# Airbeam_v2_4_12-21-2017.net
KiCad netlist of a schematic drawn in EAGLE
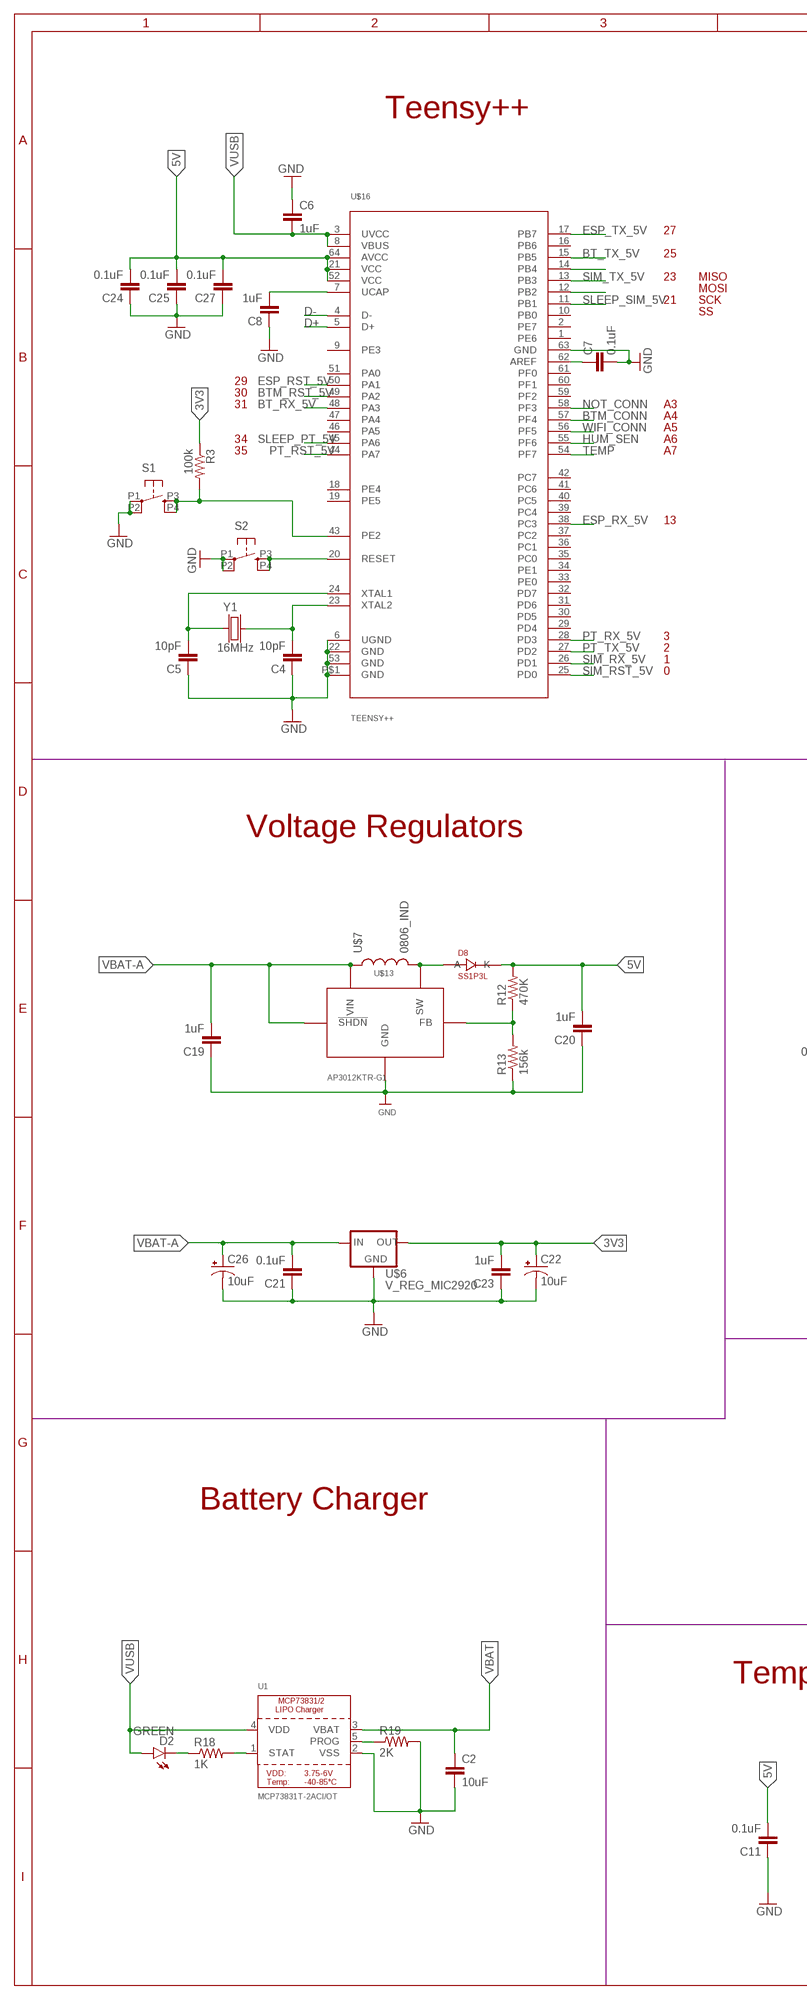
[diagram p0: schematic, sheet 1, part 1 of 2]
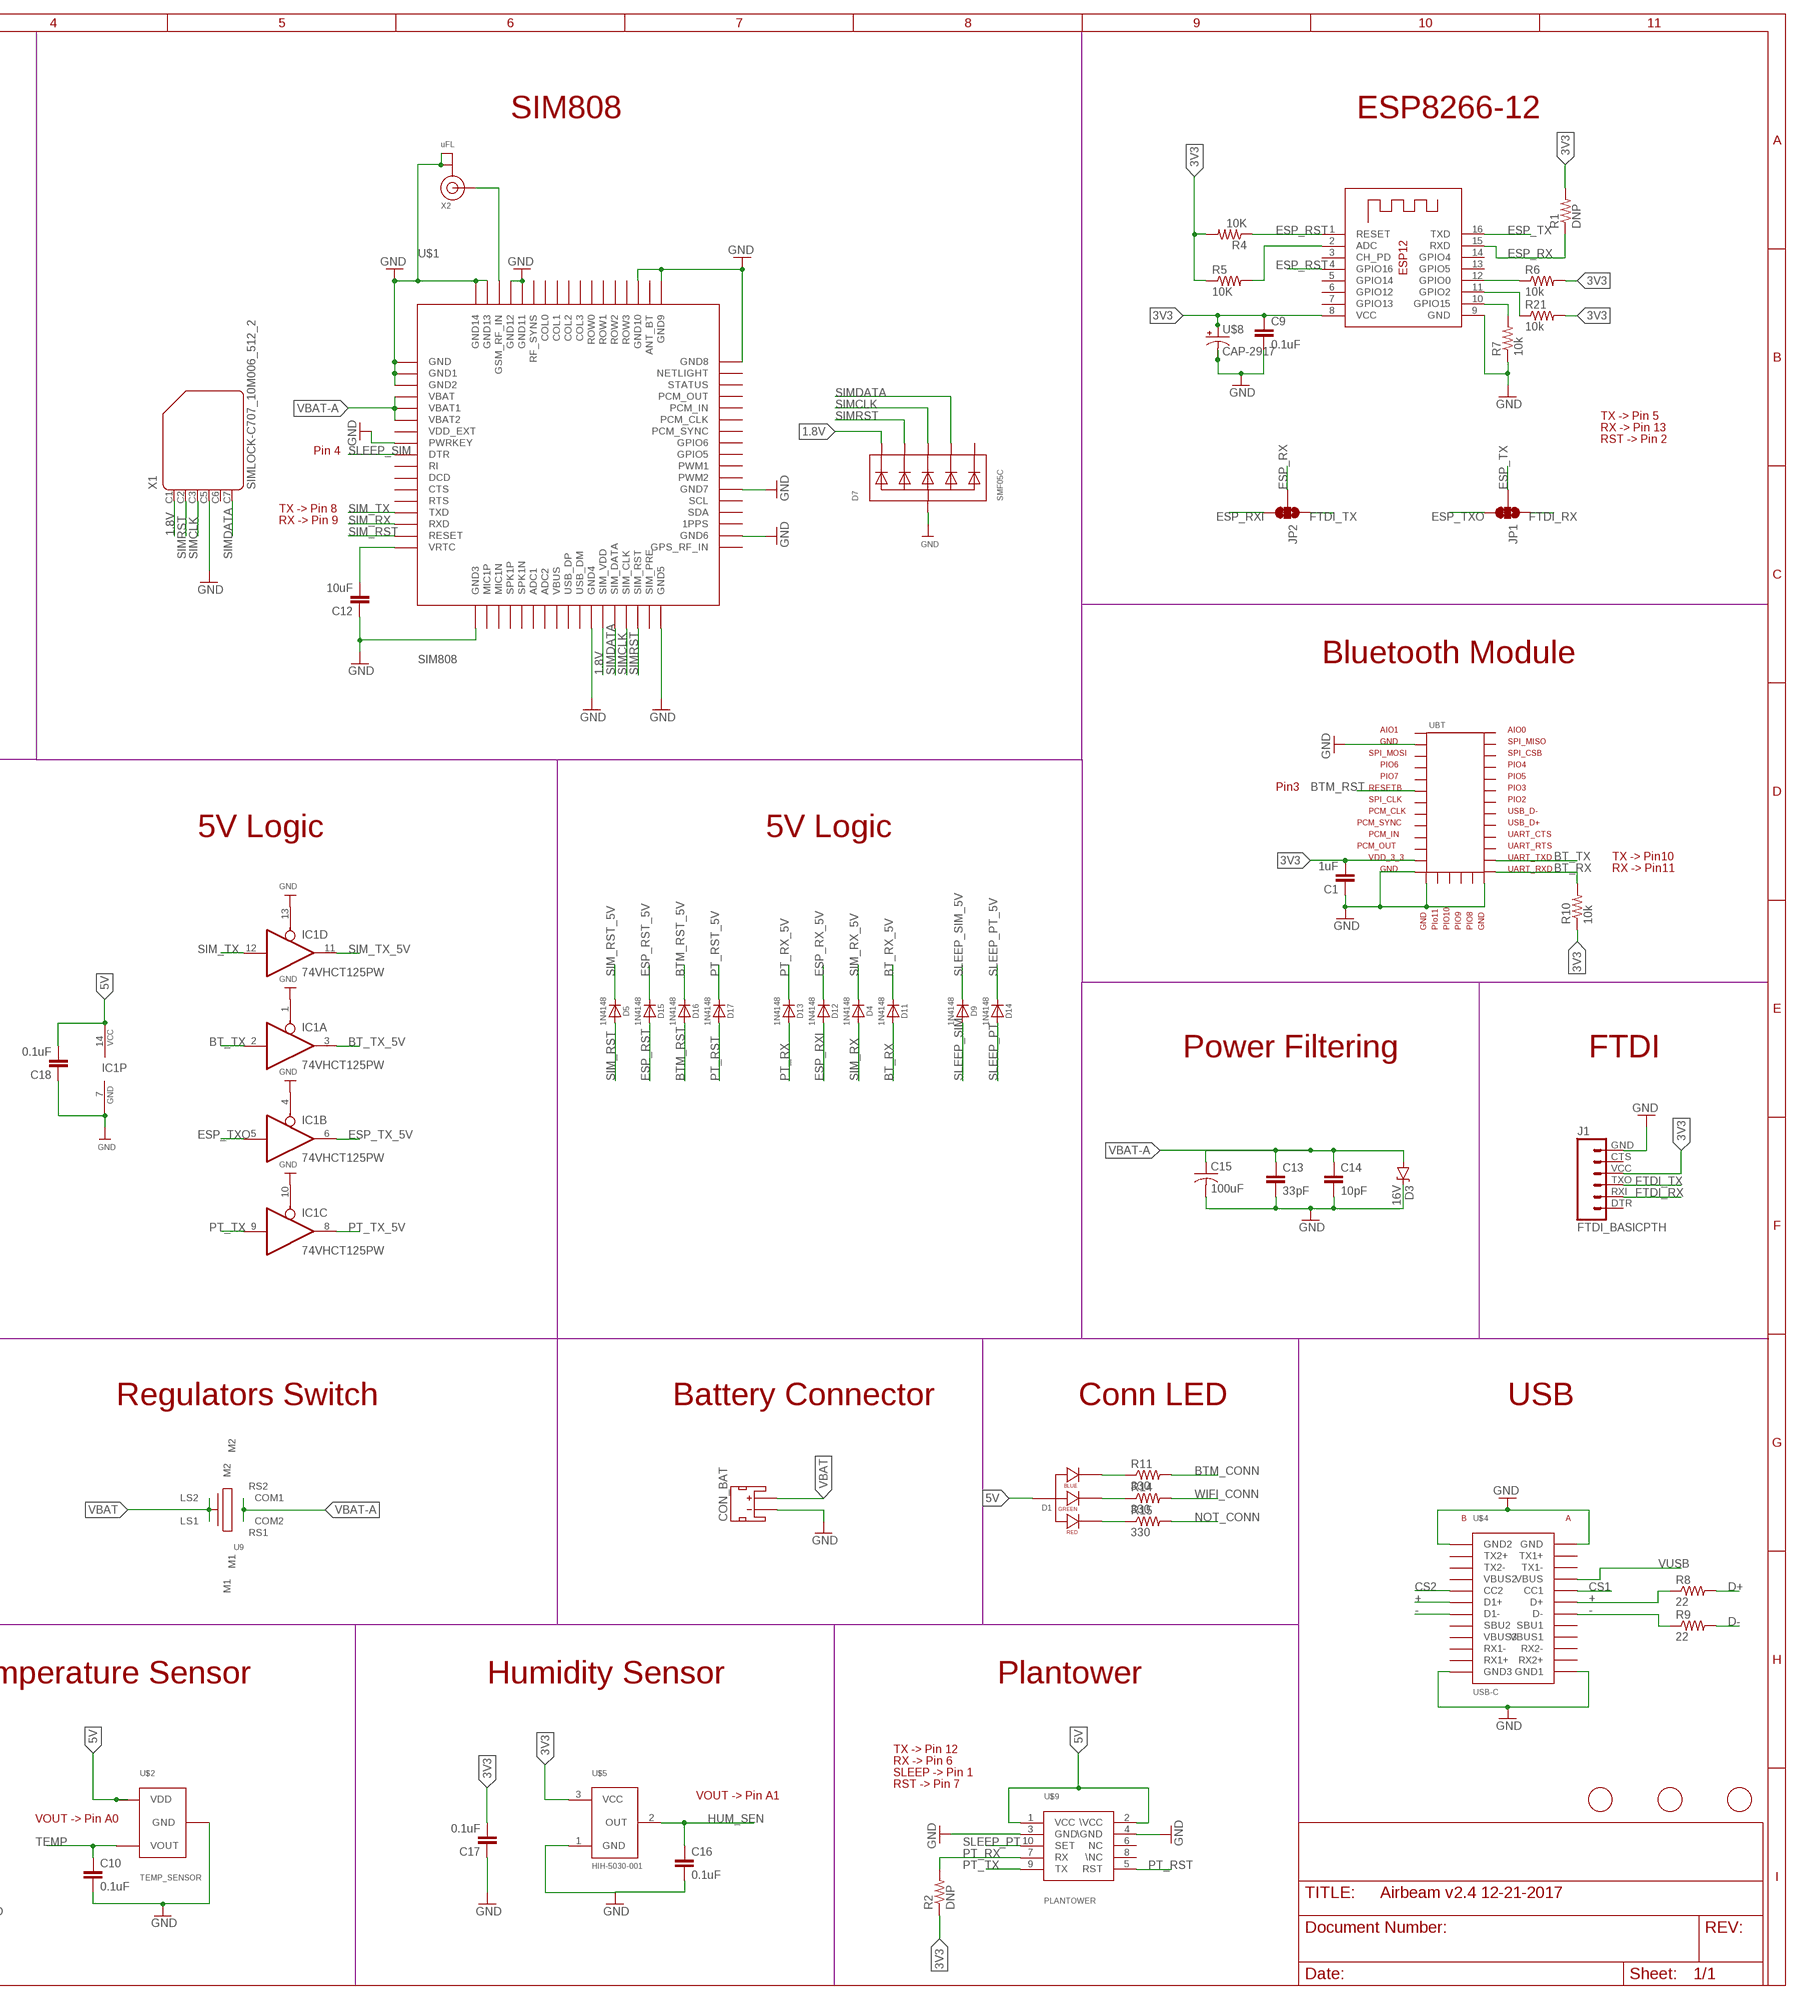
[diagram p1: schematic, sheet 1, part 2 of 2]

(export (version "E")
  (design (tool "Eeschema 10.0.6"))
  (components
    (comp (ref "C1")
      (value "1uF")
      (footprint "eagle-import:CAP0603")
      (fields (field (name "TOLERANCE") "10%") (field (name "VOLTAGE") "25V"))
      (libsource (lib "eagle-import") (part "CAP-0603-1UF-25V-10%"))
    )
    (comp (ref "C2")
      (value "10uF")
      (footprint "eagle-import:CAP0603")
      (fields (field (name "TOLERANCE") "10%") (field (name "VOLTAGE") "10V"))
      (libsource (lib "eagle-import") (part "CAP-0603-10UF-10V-10%"))
    )
    (comp (ref "C4")
      (value "10pF")
      (footprint "eagle-import:CAP0603")
      (fields (field (name "TOLERANCE") "5%") (field (name "VOLTAGE") "50V"))
      (libsource (lib "eagle-import") (part "CAP-0603-20PF-50V-5%"))
    )
    (comp (ref "C5")
      (value "10pF")
      (footprint "eagle-import:CAP0603")
      (fields (field (name "TOLERANCE") "5%") (field (name "VOLTAGE") "50V"))
      (libsource (lib "eagle-import") (part "CAP-0603-20PF-50V-5%"))
    )
    (comp (ref "C6")
      (value "1uF")
      (footprint "eagle-import:CAP0603")
      (fields (field (name "TOLERANCE") "10%") (field (name "VOLTAGE") "16V"))
      (libsource (lib "eagle-import") (part "CAP-0603-1UF-16V-10%"))
    )
    (comp (ref "C7")
      (value "0.1uF")
      (footprint "eagle-import:CAP0603")
      (fields (field (name "TOLERANCE") "5%") (field (name "VOLTAGE") "10V"))
      (libsource (lib "eagle-import") (part "CAP-0603-0.1UF-10V-5%"))
    )
    (comp (ref "C8")
      (value "1uF")
      (footprint "eagle-import:CAP0603")
      (fields (field (name "TOLERANCE") "10%") (field (name "VOLTAGE") "16V"))
      (libsource (lib "eagle-import") (part "CAP-0603-1UF-16V-10%"))
    )
    (comp (ref "C9")
      (value "0.1uF")
      (footprint "eagle-import:CAP0603")
      (fields (field (name "TOLERANCE") "5%") (field (name "VOLTAGE") "10V"))
      (libsource (lib "eagle-import") (part "CAP-0603-0.1UF-10V-5%"))
    )
    (comp (ref "C10")
      (value "0.1uF")
      (footprint "eagle-import:CAP0603")
      (fields (field (name "TOLERANCE") "5%") (field (name "VOLTAGE") "10V"))
      (libsource (lib "eagle-import") (part "CAP-0603-0.1UF-10V-5%"))
    )
    (comp (ref "C11")
      (value "0.1uF")
      (footprint "eagle-import:CAP0603")
      (fields (field (name "TOLERANCE") "5%") (field (name "VOLTAGE") "10V"))
      (libsource (lib "eagle-import") (part "CAP-0603-0.1UF-10V-5%"))
    )
    (comp (ref "C12")
      (value "10uF")
      (footprint "eagle-import:CAP0603")
      (fields (field (name "TOLERANCE") "10%") (field (name "VOLTAGE") "10V"))
      (libsource (lib "eagle-import") (part "CAP-0603-10UF-10V-10%"))
    )
    (comp (ref "C13")
      (value "33pF")
      (footprint "eagle-import:CAP0603")
      (libsource (lib "eagle-import") (part "CAP-0603-EMPTY-VALUES"))
    )
    (comp (ref "C14")
      (value "10pF")
      (footprint "eagle-import:CAP0603")
      (libsource (lib "eagle-import") (part "CAP-0603-EMPTY-VALUES"))
    )
    (comp (ref "C15")
      (value "100uF")
      (footprint "eagle-import:C1210")
      (libsource (lib "eagle-import") (part "C-USC1210"))
    )
    (comp (ref "C16")
      (value "0.1uF")
      (footprint "eagle-import:CAP0603")
      (fields (field (name "TOLERANCE") "5%") (field (name "VOLTAGE") "10V"))
      (libsource (lib "eagle-import") (part "CAP-0603-0.1UF-10V-5%"))
    )
    (comp (ref "C17")
      (value "0.1uF")
      (footprint "eagle-import:CAP0603")
      (fields (field (name "TOLERANCE") "5%") (field (name "VOLTAGE") "10V"))
      (libsource (lib "eagle-import") (part "CAP-0603-0.1UF-10V-5%"))
    )
    (comp (ref "C18")
      (value "0.1uF")
      (footprint "eagle-import:CAP0603")
      (fields (field (name "TOLERANCE") "5%") (field (name "VOLTAGE") "10V"))
      (libsource (lib "eagle-import") (part "CAP-0603-0.1UF-10V-5%"))
    )
    (comp (ref "C19")
      (value "1uF")
      (footprint "eagle-import:CAP0603")
      (fields (field (name "TOLERANCE") "10%") (field (name "VOLTAGE") "16V"))
      (libsource (lib "eagle-import") (part "CAP-0603-1UF-16V-10%"))
    )
    (comp (ref "C20")
      (value "1uF")
      (footprint "eagle-import:CAP0603")
      (fields (field (name "TOLERANCE") "10%") (field (name "VOLTAGE") "16V"))
      (libsource (lib "eagle-import") (part "CAP-0603-1UF-16V-10%"))
    )
    (comp (ref "C21")
      (value "0.1uF")
      (footprint "eagle-import:CAP0603")
      (fields (field (name "TOLERANCE") "5%") (field (name "VOLTAGE") "10V"))
      (libsource (lib "eagle-import") (part "CAP-0603-0.1UF-10V-5%"))
    )
    (comp (ref "C22")
      (value "10uF")
      (footprint "eagle-import:EIA3216")
      (libsource (lib "eagle-import") (part "CAP_POL1206"))
    )
    (comp (ref "C23")
      (value "1uF")
      (footprint "eagle-import:CAP0603")
      (fields (field (name "TOLERANCE") "10%") (field (name "VOLTAGE") "16V"))
      (libsource (lib "eagle-import") (part "CAP-0603-1UF-16V-10%"))
    )
    (comp (ref "C24")
      (value "0.1uF")
      (footprint "eagle-import:CAP0603")
      (fields (field (name "TOLERANCE") "5%") (field (name "VOLTAGE") "10V"))
      (libsource (lib "eagle-import") (part "CAP-0603-0.1UF-10V-5%"))
    )
    (comp (ref "C25")
      (value "0.1uF")
      (footprint "eagle-import:CAP0603")
      (fields (field (name "TOLERANCE") "5%") (field (name "VOLTAGE") "10V"))
      (libsource (lib "eagle-import") (part "CAP-0603-0.1UF-10V-5%"))
    )
    (comp (ref "C26")
      (value "10uF")
      (footprint "eagle-import:EIA3216")
      (libsource (lib "eagle-import") (part "CAP_POL1206"))
    )
    (comp (ref "C27")
      (value "0.1uF")
      (footprint "eagle-import:CAP0603")
      (fields (field (name "TOLERANCE") "5%") (field (name "VOLTAGE") "10V"))
      (libsource (lib "eagle-import") (part "CAP-0603-0.1UF-10V-5%"))
    )
    (comp (ref "CON_BAT")
      (value "CON_BAT")
      (footprint "eagle-import:JST-2-SMD")
      (fields (field (name "PARTNO") "S2B-PH-SM4-TB(LF)(SN)"))
      (libsource (lib "eagle-import") (part "JST_2MM_MALE"))
    )
    (comp (ref "D1")
      (value "LED1615RGBC")
      (footprint "eagle-import:LED1615RGBC")
      (libsource (lib "eagle-import") (part "LED1615RGBC"))
    )
    (comp (ref "D2")
      (value "GREEN")
      (footprint "eagle-import:LED-0603")
      (libsource (lib "eagle-import") (part "LED-GREEN-0603"))
    )
    (comp (ref "D3")
      (value "16V")
      (footprint "eagle-import:SOD-123")
      (libsource (lib "eagle-import") (part "DIODE-ZENER16V"))
    )
    (comp (ref "D4")
      (value "1N4148")
      (footprint "eagle-import:SOD-323")
      (libsource (lib "eagle-import") (part "DIODESOD-323"))
    )
    (comp (ref "D5")
      (value "1N4148")
      (footprint "eagle-import:SOD-323")
      (libsource (lib "eagle-import") (part "DIODESOD-323"))
    )
    (comp (ref "D7")
      (value "SMF05C")
      (footprint "eagle-import:SOT363")
      (libsource (lib "eagle-import") (part "TVSARRAY_5LANE"))
    )
    (comp (ref "D8")
      (value "SS1P3L")
      (footprint "eagle-import:DO220AAL")
      (libsource (lib "eagle-import") (part "SS1P3L"))
    )
    (comp (ref "D9")
      (value "1N4148")
      (footprint "eagle-import:SOD-323")
      (libsource (lib "eagle-import") (part "DIODESOD-323"))
    )
    (comp (ref "D11")
      (value "1N4148")
      (footprint "eagle-import:SOD-323")
      (libsource (lib "eagle-import") (part "DIODESOD-323"))
    )
    (comp (ref "D12")
      (value "1N4148")
      (footprint "eagle-import:SOD-323")
      (libsource (lib "eagle-import") (part "DIODESOD-323"))
    )
    (comp (ref "D13")
      (value "1N4148")
      (footprint "eagle-import:SOD-323")
      (libsource (lib "eagle-import") (part "DIODESOD-323"))
    )
    (comp (ref "D14")
      (value "1N4148")
      (footprint "eagle-import:SOD-323")
      (libsource (lib "eagle-import") (part "DIODESOD-323"))
    )
    (comp (ref "D15")
      (value "1N4148")
      (footprint "eagle-import:SOD-323")
      (libsource (lib "eagle-import") (part "DIODESOD-323"))
    )
    (comp (ref "D16")
      (value "1N4148")
      (footprint "eagle-import:SOD-323")
      (libsource (lib "eagle-import") (part "DIODESOD-323"))
    )
    (comp (ref "D17")
      (value "1N4148")
      (footprint "eagle-import:SOD-323")
      (libsource (lib "eagle-import") (part "DIODESOD-323"))
    )
    (comp (ref "IC1")
      (value "74VHCT125PW")
      (footprint "eagle-import:TSSOP14")
      (libsource (lib "eagle-import") (part "74125PWABT"))
    )
    (comp (ref "J1")
      (value "FTDI_BASICPTH")
      (footprint "eagle-import:FTDI_BASIC")
      (libsource (lib "eagle-import") (part "FTDI_BASICPTH"))
    )
    (comp (ref "JP1")
      (value "JUMPER-PAD-3-2OF3_NC_BY_TRACE_SMALL")
      (footprint "eagle-import:PAD-JUMPER-3-2OF3_NC_BY_TRACE_YES_SILK_FULL_BOX")
      (libsource (lib "eagle-import") (part "JUMPER-PAD-3-2OF3_NC_BY_TRACE_SMALL"))
    )
    (comp (ref "JP2")
      (value "JUMPER-PAD-3-2OF3_NC_BY_TRACE_SMALL")
      (footprint "eagle-import:PAD-JUMPER-3-2OF3_NC_BY_TRACE_YES_SILK_FULL_BOX")
      (libsource (lib "eagle-import") (part "JUMPER-PAD-3-2OF3_NC_BY_TRACE_SMALL"))
    )
    (comp (ref "R1")
      (value "DNP")
      (footprint "eagle-import:RES-0603")
      (libsource (lib "eagle-import") (part "RES-0603_EMPTY-FIELDS"))
    )
    (comp (ref "R2")
      (value "DNP")
      (footprint "eagle-import:RES-0603")
      (libsource (lib "eagle-import") (part "RES-0603_EMPTY-FIELDS"))
    )
    (comp (ref "R3")
      (value "100k")
      (footprint "eagle-import:RES-0603")
      (libsource (lib "eagle-import") (part "RES-0603_EMPTY-FIELDS"))
    )
    (comp (ref "R4")
      (value "10K")
      (footprint "eagle-import:RES-0603")
      (fields (field (name "TOLERANCE") "5%"))
      (libsource (lib "eagle-import") (part "RES-0603-10K-5%"))
    )
    (comp (ref "R5")
      (value "10K")
      (footprint "eagle-import:RES-0603")
      (fields (field (name "TOLERANCE") "5%"))
      (libsource (lib "eagle-import") (part "RES-0603-10K-5%"))
    )
    (comp (ref "R6")
      (value "10k")
      (footprint "eagle-import:RES-0603")
      (libsource (lib "eagle-import") (part "RES-0603_EMPTY-FIELDS"))
    )
    (comp (ref "R7")
      (value "10k")
      (footprint "eagle-import:RES-0603")
      (libsource (lib "eagle-import") (part "RES-0603_EMPTY-FIELDS"))
    )
    (comp (ref "R8")
      (value "22")
      (footprint "eagle-import:RES-0603")
      (fields (field (name "TOLERANCE") "5%"))
      (libsource (lib "eagle-import") (part "RES-0603-22-5%"))
    )
    (comp (ref "R9")
      (value "22")
      (footprint "eagle-import:RES-0603")
      (fields (field (name "TOLERANCE") "5%"))
      (libsource (lib "eagle-import") (part "RES-0603-22-5%"))
    )
    (comp (ref "R10")
      (value "10k")
      (footprint "eagle-import:RES-0603")
      (libsource (lib "eagle-import") (part "RES-0603_EMPTY-FIELDS"))
    )
    (comp (ref "R11")
      (value "330")
      (footprint "eagle-import:RES-0603")
      (fields (field (name "TOLERANCE") "5%"))
      (libsource (lib "eagle-import") (part "RES-0603-22-5%"))
    )
    (comp (ref "R12")
      (value "470K")
      (footprint "eagle-import:RES-0603")
      (fields (field (name "TOLERANCE") "5%"))
      (libsource (lib "eagle-import") (part "RES-0603-470K-5%"))
    )
    (comp (ref "R13")
      (value "156k")
      (footprint "eagle-import:RES-0603")
      (libsource (lib "eagle-import") (part "RES-0603_EMPTY-FIELDS"))
    )
    (comp (ref "R14")
      (value "330")
      (footprint "eagle-import:RES-0603")
      (fields (field (name "TOLERANCE") "5%"))
      (libsource (lib "eagle-import") (part "RES-0603-22-5%"))
    )
    (comp (ref "R15")
      (value "330")
      (footprint "eagle-import:RES-0603")
      (fields (field (name "TOLERANCE") "5%"))
      (libsource (lib "eagle-import") (part "RES-0603-22-5%"))
    )
    (comp (ref "R18")
      (value "1K")
      (footprint "eagle-import:RES-0603")
      (fields (field (name "TOLERANCE") "5%"))
      (libsource (lib "eagle-import") (part "RES-0603-1K-5%"))
    )
    (comp (ref "R19")
      (value "2K")
      (footprint "eagle-import:RES-0603")
      (fields (field (name "TOLERANCE") "1%"))
      (libsource (lib "eagle-import") (part "RES-0603-2K-1%"))
    )
    (comp (ref "R21")
      (value "10k")
      (footprint "eagle-import:RES-0603")
      (libsource (lib "eagle-import") (part "RES-0603_EMPTY-FIELDS"))
    )
    (comp (ref "S1")
      (value "JAYCONSYSTEMS_TAC_SWITCHHIRO")
      (footprint "eagle-import:JAYCONSYSTEMS_TS-1184")
      (libsource (lib "eagle-import") (part "JAYCONSYSTEMS_TAC_SWITCHHIRO"))
    )
    (comp (ref "S2")
      (value "JAYCONSYSTEMS_TAC_SWITCHHIRO")
      (footprint "eagle-import:JAYCONSYSTEMS_TS-1184")
      (libsource (lib "eagle-import") (part "JAYCONSYSTEMS_TAC_SWITCHHIRO"))
    )
    (comp (ref "U$1")
      (value "SIM808")
      (footprint "eagle-import:SIM808")
      (libsource (lib "eagle-import") (part "SIM808"))
    )
    (comp (ref "U$2")
      (value "TEMP_SENSOR")
      (footprint "eagle-import:SOT23-3")
      (libsource (lib "eagle-import") (part "TEMP_SENSOR"))
    )
    (comp (ref "U$3")
      (value "FIDUCIAL")
      (footprint "eagle-import:FIDUCIAL_1MM")
      (libsource (lib "eagle-import") (part "FIDUCIAL"))
    )
    (comp (ref "U$4")
      (value "USB-C")
      (footprint "eagle-import:USB-C")
      (libsource (lib "eagle-import") (part "USB-C"))
    )
    (comp (ref "U$5")
      (value "HIH-5030-001")
      (footprint "eagle-import:HUM_SEN")
      (libsource (lib "eagle-import") (part "HIH-5030-001"))
    )
    (comp (ref "U$6")
      (value "V_REG_MIC2920")
      (footprint "eagle-import:SOT223")
      (libsource (lib "eagle-import") (part "V_REG_MIC2920"))
    )
    (comp (ref "U$7")
      (value "0806_IND")
      (footprint "eagle-import:0806")
      (libsource (lib "eagle-import") (part "0806_IND"))
    )
    (comp (ref "U$8")
      (value "CAP-2917")
      (footprint "eagle-import:EIA2917")
      (libsource (lib "eagle-import") (part "CAP-2917"))
    )
    (comp (ref "U$9")
      (value "PLANTOWER")
      (footprint "eagle-import:CONN")
      (libsource (lib "eagle-import") (part "PLANTOWER"))
    )
    (comp (ref "U$12")
      (value "FIDUCIAL")
      (footprint "eagle-import:FIDUCIAL_1MM")
      (libsource (lib "eagle-import") (part "FIDUCIAL"))
    )
    (comp (ref "U$13")
      (value "AP3012KTR-G1")
      (footprint "eagle-import:SOT23-5")
      (libsource (lib "eagle-import") (part "AP3012KTR-G1"))
    )
    (comp (ref "U$14")
      (value "FIDUCIAL")
      (footprint "eagle-import:FIDUCIAL_1MM")
      (libsource (lib "eagle-import") (part "FIDUCIAL"))
    )
    (comp (ref "U$16")
      (value "TEENSY++")
      (footprint "eagle-import:64QFN")
      (libsource (lib "eagle-import") (part "TEENSY++"))
    )
    (comp (ref "U1")
      (value "MCP73831T-2ACI/OT")
      (footprint "eagle-import:SOT23-5")
      (libsource (lib "eagle-import") (part "MCP73831/2"))
    )
    (comp (ref "U9")
      (value "PUSHBUTTON")
      (footprint "eagle-import:PUSHBUTTON")
      (fields (field (name "PARTNO") "LC2259EENP"))
      (libsource (lib "eagle-import") (part "PUSHBUTTON"))
    )
    (comp (ref "UBT")
      (value "BT-NVC-MDCS42A")
      (footprint "eagle-import:BT_NVC-MDCS42A")
      (fields (field (name "PARTNO") "NVC-MDCS42A"))
      (libsource (lib "eagle-import") (part "BT-NVC-MDCS42A"))
    )
    (comp (ref "X1")
      (value "SIMLOCK-C707_10M006_512_2")
      (footprint "eagle-import:C707_10M006_512_2")
      (libsource (lib "eagle-import") (part "SIMLOCK-C707_10M006_512_2"))
    )
    (comp (ref "X2")
      (value "uFL")
      (footprint "eagle-import:U.FL")
      (libsource (lib "eagle-import") (part "ANTENNA_U.FL"))
    )
    (comp (ref "X3")
      (value "ESP-12")
      (footprint "eagle-import:ESP-12")
      (libsource (lib "eagle-import") (part "ESP-12"))
    )
    (comp (ref "Y1")
      (value "16MHz")
      (footprint "eagle-import:CRYSTAL-3.2X2.5")
      (libsource (lib "eagle-import") (part "OSCILLATOR"))
    )
  )
  (nets
    (net (code "1") (name "/+") (class "Default")
      (node (ref "R8") (pin "1") (pinfunction "1_1") (pintype "passive"))
      (node (ref "U$4") (pin "A6") (pinfunction "D+_A6") (pintype "bidirectional"))
      (node (ref "U$4") (pin "B6") (pinfunction "D1+_B6") (pintype "bidirectional"))
    )
    (net (code "2") (name "/-") (class "Default")
      (node (ref "R9") (pin "1") (pinfunction "1_1") (pintype "passive"))
      (node (ref "U$4") (pin "A7") (pinfunction "D-_A7") (pintype "bidirectional"))
      (node (ref "U$4") (pin "B7") (pinfunction "D1-_B7") (pintype "bidirectional"))
    )
    (net (code "3") (name "/BTM_CONN") (class "Default")
      (node (ref "R11") (pin "2") (pinfunction "2_2") (pintype "passive"))
      (node (ref "U$16") (pin "57") (pinfunction "PF4_57") (pintype "bidirectional"))
    )
    (net (code "4") (name "/BTM_RST") (class "Default")
      (node (ref "D16") (pin "A") (pinfunction "A_A") (pintype "passive"))
      (node (ref "UBT") (pin "P$6") (pinfunction "P$6_P$6") (pintype "bidirectional"))
    )
    (net (code "5") (name "/BTM_RST_5V") (class "Default")
      (node (ref "D16") (pin "C") (pinfunction "C_C") (pintype "passive"))
      (node (ref "U$16") (pin "49") (pinfunction "PA2_49") (pintype "bidirectional"))
    )
    (net (code "6") (name "/BT_RX") (class "Default")
      (node (ref "D11") (pin "A") (pinfunction "A_A") (pintype "passive"))
      (node (ref "R10") (pin "2") (pinfunction "2_2") (pintype "passive"))
      (node (ref "UBT") (pin "P$20") (pinfunction "P$20_P$20") (pintype "bidirectional"))
    )
    (net (code "7") (name "/BT_RX_5V") (class "Default")
      (node (ref "D11") (pin "C") (pinfunction "C_C") (pintype "passive"))
      (node (ref "U$16") (pin "48") (pinfunction "PA3_48") (pintype "bidirectional"))
    )
    (net (code "8") (name "/BT_TX") (class "Default")
      (node (ref "IC1") (pin "2") (pinfunction "I_2") (pintype "input"))
      (node (ref "UBT") (pin "P$21") (pinfunction "P$21_P$21") (pintype "bidirectional"))
    )
    (net (code "9") (name "/BT_TX_5V") (class "Default")
      (node (ref "IC1") (pin "3") (pinfunction "O_3") (pintype "tri_state"))
      (node (ref "U$16") (pin "15") (pinfunction "PB5_15") (pintype "bidirectional"))
    )
    (net (code "10") (name "/CS1") (class "Default")
      (node (ref "U$4") (pin "A5") (pinfunction "CC1_A5") (pintype "bidirectional"))
    )
    (net (code "11") (name "/CS2") (class "Default")
      (node (ref "U$4") (pin "B5") (pinfunction "CC2_B5") (pintype "bidirectional"))
    )
    (net (code "12") (name "/D+") (class "Default")
      (node (ref "R8") (pin "2") (pinfunction "2_2") (pintype "passive"))
      (node (ref "U$16") (pin "5") (pinfunction "D+_5") (pintype "bidirectional"))
    )
    (net (code "13") (name "/D-") (class "Default")
      (node (ref "R9") (pin "2") (pinfunction "2_2") (pintype "passive"))
      (node (ref "U$16") (pin "4") (pinfunction "D-_4") (pintype "bidirectional"))
    )
    (net (code "14") (name "/ESP_RST") (class "Default")
      (node (ref "D15") (pin "A") (pinfunction "A_A") (pintype "passive"))
      (node (ref "R4") (pin "1") (pinfunction "1_1") (pintype "passive"))
      (node (ref "X3") (pin "1") (pinfunction "RESET_1") (pintype "input"))
      (node (ref "X3") (pin "4") (pinfunction "GPIO16_4") (pintype "bidirectional"))
    )
    (net (code "15") (name "/ESP_RST_5V") (class "Default")
      (node (ref "D15") (pin "C") (pinfunction "C_C") (pintype "passive"))
      (node (ref "U$16") (pin "50") (pinfunction "PA1_50") (pintype "bidirectional"))
    )
    (net (code "16") (name "/ESP_RX") (class "Default")
      (node (ref "JP2") (pin "2") (pinfunction "2_2") (pintype "passive"))
      (node (ref "R1") (pin "1") (pinfunction "1_1") (pintype "passive"))
      (node (ref "X3") (pin "15") (pinfunction "RXD_15") (pintype "input"))
    )
    (net (code "17") (name "/ESP_RXI") (class "Default")
      (node (ref "D12") (pin "A") (pinfunction "A_A") (pintype "passive"))
      (node (ref "JP2") (pin "3") (pinfunction "3_3") (pintype "passive"))
    )
    (net (code "18") (name "/ESP_RX_5V") (class "Default")
      (node (ref "D12") (pin "C") (pinfunction "C_C") (pintype "passive"))
      (node (ref "U$16") (pin "38") (pinfunction "PC3_38") (pintype "bidirectional"))
    )
    (net (code "19") (name "/ESP_TX") (class "Default")
      (node (ref "JP1") (pin "2") (pinfunction "2_2") (pintype "passive"))
      (node (ref "X3") (pin "16") (pinfunction "TXD_16") (pintype "output"))
    )
    (net (code "20") (name "/ESP_TXO") (class "Default")
      (node (ref "IC1") (pin "5") (pinfunction "I_5") (pintype "input"))
      (node (ref "JP1") (pin "3") (pinfunction "3_3") (pintype "passive"))
    )
    (net (code "21") (name "/ESP_TX_5V") (class "Default")
      (node (ref "IC1") (pin "6") (pinfunction "O_6") (pintype "tri_state"))
      (node (ref "U$16") (pin "17") (pinfunction "PB7_17") (pintype "bidirectional"))
    )
    (net (code "22") (name "/FTDI_RX") (class "Default")
      (node (ref "J1") (pin "RXI") (pinfunction "2_RXI") (pintype "passive"))
      (node (ref "JP1") (pin "1") (pinfunction "1_1") (pintype "passive"))
    )
    (net (code "23") (name "/FTDI_TX") (class "Default")
      (node (ref "J1") (pin "TXO") (pinfunction "3_TXO") (pintype "passive"))
      (node (ref "JP2") (pin "1") (pinfunction "1_1") (pintype "passive"))
    )
    (net (code "24") (name "/HUM_SEN") (class "Default")
      (node (ref "C16") (pin "1") (pinfunction "1_1") (pintype "passive"))
      (node (ref "U$16") (pin "55") (pinfunction "PF6_55") (pintype "bidirectional"))
      (node (ref "U$5") (pin "2") (pinfunction "OUT_2") (pintype "bidirectional"))
    )
    (net (code "25") (name "/NOT_CONN") (class "Default")
      (node (ref "R15") (pin "2") (pinfunction "2_2") (pintype "passive"))
      (node (ref "U$16") (pin "58") (pinfunction "PF3_58") (pintype "bidirectional"))
    )
    (net (code "26") (name "/PT_RST") (class "Default")
      (node (ref "D17") (pin "A") (pinfunction "A_A") (pintype "passive"))
      (node (ref "U$9") (pin "5") (pinfunction "RST_5") (pintype "bidirectional"))
    )
    (net (code "27") (name "/PT_RST_5V") (class "Default")
      (node (ref "D17") (pin "C") (pinfunction "C_C") (pintype "passive"))
      (node (ref "U$16") (pin "44") (pinfunction "PA7_44") (pintype "bidirectional"))
    )
    (net (code "28") (name "/PT_RX") (class "Default")
      (node (ref "D13") (pin "A") (pinfunction "A_A") (pintype "passive"))
      (node (ref "R2") (pin "2") (pinfunction "2_2") (pintype "passive"))
      (node (ref "U$9") (pin "7") (pinfunction "RX_7") (pintype "bidirectional"))
    )
    (net (code "29") (name "/PT_RX_5V") (class "Default")
      (node (ref "D13") (pin "C") (pinfunction "C_C") (pintype "passive"))
      (node (ref "U$16") (pin "28") (pinfunction "PD3_28") (pintype "bidirectional"))
    )
    (net (code "30") (name "/PT_TX") (class "Default")
      (node (ref "IC1") (pin "9") (pinfunction "I_9") (pintype "input"))
      (node (ref "U$9") (pin "9") (pinfunction "TX_9") (pintype "bidirectional"))
    )
    (net (code "31") (name "/PT_TX_5V") (class "Default")
      (node (ref "IC1") (pin "8") (pinfunction "O_8") (pintype "tri_state"))
      (node (ref "U$16") (pin "27") (pinfunction "PD2_27") (pintype "bidirectional"))
    )
    (net (code "32") (name "/SIMCLK") (class "Default")
      (node (ref "D7") (pin "4") (pinfunction "C3_4") (pintype "passive"))
      (node (ref "U$1") (pin "31") (pinfunction "SIM_CLK_31") (pintype "bidirectional"))
      (node (ref "X1") (pin "C3") (pinfunction "3_C3") (pintype "passive"))
    )
    (net (code "33") (name "/SIMDATA") (class "Default")
      (node (ref "D7") (pin "5") (pinfunction "C4_5") (pintype "passive"))
      (node (ref "U$1") (pin "30") (pinfunction "SIM_DATA_30") (pintype "bidirectional"))
      (node (ref "X1") (pin "C7") (pinfunction "6_C7") (pintype "passive"))
    )
    (net (code "34") (name "/SIMRST") (class "Default")
      (node (ref "D7") (pin "3") (pinfunction "C2_3") (pintype "passive"))
      (node (ref "U$1") (pin "32") (pinfunction "SIM_RST_32") (pintype "bidirectional"))
      (node (ref "X1") (pin "C2") (pinfunction "2_C2") (pintype "passive"))
    )
    (net (code "35") (name "/SIM_RST") (class "Default")
      (node (ref "D5") (pin "A") (pinfunction "A_A") (pintype "passive"))
      (node (ref "U$1") (pin "16") (pinfunction "RESET_16") (pintype "bidirectional"))
    )
    (net (code "36") (name "/SIM_RST_5V") (class "Default")
      (node (ref "D5") (pin "C") (pinfunction "C_C") (pintype "passive"))
      (node (ref "U$16") (pin "25") (pinfunction "PD0_25") (pintype "bidirectional"))
    )
    (net (code "37") (name "/SIM_RX") (class "Default")
      (node (ref "D4") (pin "A") (pinfunction "A_A") (pintype "passive"))
      (node (ref "U$1") (pin "15") (pinfunction "RXD_15") (pintype "bidirectional"))
    )
    (net (code "38") (name "/SIM_RX_5V") (class "Default")
      (node (ref "D4") (pin "C") (pinfunction "C_C") (pintype "passive"))
      (node (ref "U$16") (pin "26") (pinfunction "PD1_26") (pintype "bidirectional"))
    )
    (net (code "39") (name "/SIM_TX") (class "Default")
      (node (ref "IC1") (pin "12") (pinfunction "I_12") (pintype "input"))
      (node (ref "U$1") (pin "14") (pinfunction "TXD_14") (pintype "bidirectional"))
    )
    (net (code "40") (name "/SIM_TX_5V") (class "Default")
      (node (ref "IC1") (pin "11") (pinfunction "O_11") (pintype "tri_state"))
      (node (ref "U$16") (pin "13") (pinfunction "PB3_13") (pintype "bidirectional"))
    )
    (net (code "41") (name "/SLEEP_PT") (class "Default")
      (node (ref "D14") (pin "A") (pinfunction "A_A") (pintype "passive"))
      (node (ref "U$9") (pin "10") (pinfunction "SET_10") (pintype "bidirectional"))
    )
    (net (code "42") (name "/SLEEP_PT_5V") (class "Default")
      (node (ref "D14") (pin "C") (pinfunction "C_C") (pintype "passive"))
      (node (ref "U$16") (pin "45") (pinfunction "PA6_45") (pintype "bidirectional"))
    )
    (net (code "43") (name "/SLEEP_SIM") (class "Default")
      (node (ref "D9") (pin "A") (pinfunction "A_A") (pintype "passive"))
      (node (ref "U$1") (pin "9") (pinfunction "DTR_9") (pintype "bidirectional"))
    )
    (net (code "44") (name "/SLEEP_SIM_5V") (class "Default")
      (node (ref "D9") (pin "C") (pinfunction "C_C") (pintype "passive"))
      (node (ref "U$16") (pin "11") (pinfunction "PB1_11") (pintype "bidirectional"))
    )
    (net (code "45") (name "/TEMP") (class "Default")
      (node (ref "C10") (pin "1") (pinfunction "1_1") (pintype "passive"))
      (node (ref "U$16") (pin "54") (pinfunction "PF7_54") (pintype "bidirectional"))
      (node (ref "U$2") (pin "2") (pinfunction "VOUT_2") (pintype "bidirectional"))
    )
    (net (code "46") (name "/WIFI_CONN") (class "Default")
      (node (ref "R14") (pin "2") (pinfunction "2_2") (pintype "passive"))
      (node (ref "U$16") (pin "56") (pinfunction "PF5_56") (pintype "bidirectional"))
    )
    (net (code "47") (name "1.8V") (class "Default")
      (node (ref "D7") (pin "1") (pinfunction "C1_1") (pintype "passive"))
      (node (ref "U$1") (pin "29") (pinfunction "SIM_VDD_29") (pintype "bidirectional"))
      (node (ref "X1") (pin "C1") (pinfunction "1_C1") (pintype "passive"))
    )
    (net (code "48") (name "3V3") (class "Default")
      (node (ref "C1") (pin "2") (pinfunction "2_2") (pintype "passive"))
      (node (ref "C17") (pin "2") (pinfunction "2_2") (pintype "passive"))
      (node (ref "C22") (pin "A") (pinfunction "+_A") (pintype "passive"))
      (node (ref "C23") (pin "2") (pinfunction "2_2") (pintype "passive"))
      (node (ref "C9") (pin "1") (pinfunction "1_1") (pintype "passive"))
      (node (ref "J1") (pin "VCC") (pinfunction "4_VCC") (pintype "passive"))
      (node (ref "R1") (pin "2") (pinfunction "2_2") (pintype "passive"))
      (node (ref "R10") (pin "1") (pinfunction "1_1") (pintype "passive"))
      (node (ref "R2") (pin "1") (pinfunction "1_1") (pintype "passive"))
      (node (ref "R21") (pin "2") (pinfunction "2_2") (pintype "passive"))
      (node (ref "R3") (pin "1") (pinfunction "1_1") (pintype "passive"))
      (node (ref "R4") (pin "2") (pinfunction "2_2") (pintype "passive"))
      (node (ref "R5") (pin "1") (pinfunction "1_1") (pintype "passive"))
      (node (ref "R6") (pin "2") (pinfunction "2_2") (pintype "passive"))
      (node (ref "U$5") (pin "3") (pinfunction "VCC_3") (pintype "bidirectional"))
      (node (ref "U$6") (pin "3") (pinfunction "OUT_3") (pintype "output"))
      (node (ref "U$8") (pin "1") (pinfunction "+_1") (pintype "passive"))
      (node (ref "UBT") (pin "P$12") (pinfunction "P$12_P$12") (pintype "bidirectional"))
      (node (ref "X3") (pin "8") (pinfunction "VCC_8") (pintype "power_in"))
    )
    (net (code "49") (name "5V") (class "Default")
      (node (ref "C11") (pin "2") (pinfunction "2_2") (pintype "passive"))
      (node (ref "C18") (pin "2") (pinfunction "2_2") (pintype "passive"))
      (node (ref "C20") (pin "2") (pinfunction "2_2") (pintype "passive"))
      (node (ref "C24") (pin "2") (pinfunction "2_2") (pintype "passive"))
      (node (ref "C25") (pin "2") (pinfunction "2_2") (pintype "passive"))
      (node (ref "C27") (pin "2") (pinfunction "2_2") (pintype "passive"))
      (node (ref "D1") (pin "1") (pinfunction "ANODE_1") (pintype "bidirectional"))
      (node (ref "D8") (pin "P$1") (pinfunction "K_P$1") (pintype "bidirectional"))
      (node (ref "IC1") (pin "14") (pinfunction "VCC_14") (pintype "power_in"))
      (node (ref "R12") (pin "2") (pinfunction "2_2") (pintype "passive"))
      (node (ref "U$16") (pin "21") (pinfunction "VCC_21") (pintype "bidirectional"))
      (node (ref "U$16") (pin "52") (pinfunction "VCC_52") (pintype "bidirectional"))
      (node (ref "U$16") (pin "64") (pinfunction "AVCC_64") (pintype "bidirectional"))
      (node (ref "U$2") (pin "1") (pinfunction "VDD_1") (pintype "bidirectional"))
      (node (ref "U$9") (pin "1") (pinfunction "VCC_1") (pintype "bidirectional"))
      (node (ref "U$9") (pin "2") (pinfunction "\\VCC_2") (pintype "bidirectional"))
    )
    (net (code "50") (name "GND") (class "Default")
      (node (ref "C1") (pin "1") (pinfunction "1_1") (pintype "passive"))
      (node (ref "C10") (pin "2") (pinfunction "2_2") (pintype "passive"))
      (node (ref "C11") (pin "1") (pinfunction "1_1") (pintype "passive"))
      (node (ref "C12") (pin "1") (pinfunction "1_1") (pintype "passive"))
      (node (ref "C13") (pin "2") (pinfunction "2_2") (pintype "passive"))
      (node (ref "C14") (pin "2") (pinfunction "2_2") (pintype "passive"))
      (node (ref "C15") (pin "2") (pinfunction "2_2") (pintype "passive"))
      (node (ref "C16") (pin "2") (pinfunction "2_2") (pintype "passive"))
      (node (ref "C17") (pin "1") (pinfunction "1_1") (pintype "passive"))
      (node (ref "C18") (pin "1") (pinfunction "1_1") (pintype "passive"))
      (node (ref "C19") (pin "1") (pinfunction "1_1") (pintype "passive"))
      (node (ref "C2") (pin "2") (pinfunction "2_2") (pintype "passive"))
      (node (ref "C20") (pin "1") (pinfunction "1_1") (pintype "passive"))
      (node (ref "C21") (pin "1") (pinfunction "1_1") (pintype "passive"))
      (node (ref "C22") (pin "C") (pinfunction "-_C") (pintype "passive"))
      (node (ref "C23") (pin "1") (pinfunction "1_1") (pintype "passive"))
      (node (ref "C24") (pin "1") (pinfunction "1_1") (pintype "passive"))
      (node (ref "C25") (pin "1") (pinfunction "1_1") (pintype "passive"))
      (node (ref "C26") (pin "C") (pinfunction "-_C") (pintype "passive"))
      (node (ref "C27") (pin "1") (pinfunction "1_1") (pintype "passive"))
      (node (ref "C4") (pin "1") (pinfunction "1_1") (pintype "passive"))
      (node (ref "C5") (pin "1") (pinfunction "1_1") (pintype "passive"))
      (node (ref "C6") (pin "1") (pinfunction "1_1") (pintype "passive"))
      (node (ref "C7") (pin "2") (pinfunction "2_2") (pintype "passive"))
      (node (ref "C8") (pin "1") (pinfunction "1_1") (pintype "passive"))
      (node (ref "C9") (pin "2") (pinfunction "2_2") (pintype "passive"))
      (node (ref "CON_BAT") (pin "1") (pinfunction "-_1") (pintype "bidirectional"))
      (node (ref "D3") (pin "C") (pinfunction "C_C") (pintype "passive"))
      (node (ref "D7") (pin "2") (pinfunction "A_2") (pintype "passive"))
      (node (ref "IC1") (pin "1") (pinfunction "OE_1") (pintype "input"))
      (node (ref "IC1") (pin "10") (pinfunction "OE_10") (pintype "input"))
      (node (ref "IC1") (pin "13") (pinfunction "OE_13") (pintype "input"))
      (node (ref "IC1") (pin "4") (pinfunction "OE_4") (pintype "input"))
      (node (ref "IC1") (pin "7") (pinfunction "GND_7") (pintype "power_in"))
      (node (ref "J1") (pin "GND") (pinfunction "6_GND") (pintype "passive"))
      (node (ref "R13") (pin "1") (pinfunction "1_1") (pintype "passive"))
      (node (ref "R19") (pin "2") (pinfunction "2_2") (pintype "passive"))
      (node (ref "R7") (pin "1") (pinfunction "1_1") (pintype "passive"))
      (node (ref "S1") (pin "P1") (pinfunction "1_P1") (pintype "passive"))
      (node (ref "S1") (pin "P2") (pinfunction "2_P2") (pintype "passive"))
      (node (ref "S2") (pin "P1") (pinfunction "1_P1") (pintype "passive"))
      (node (ref "S2") (pin "P2") (pinfunction "2_P2") (pintype "passive"))
      (node (ref "U$1") (pin "1") (pinfunction "GND_1") (pintype "bidirectional"))
      (node (ref "U$1") (pin "18") (pinfunction "GND3_18") (pintype "bidirectional"))
      (node (ref "U$1") (pin "2") (pinfunction "GND1_2") (pintype "bidirectional"))
      (node (ref "U$1") (pin "28") (pinfunction "GND4_28") (pintype "bidirectional"))
      (node (ref "U$1") (pin "3") (pinfunction "GND2_3") (pintype "bidirectional"))
      (node (ref "U$1") (pin "34") (pinfunction "GND5_34") (pintype "bidirectional"))
      (node (ref "U$1") (pin "36") (pinfunction "GND6_36") (pintype "bidirectional"))
      (node (ref "U$1") (pin "40") (pinfunction "GND7_40") (pintype "bidirectional"))
      (node (ref "U$1") (pin "51") (pinfunction "GND8_51") (pintype "bidirectional"))
      (node (ref "U$1") (pin "52") (pinfunction "GND9_52") (pintype "bidirectional"))
      (node (ref "U$1") (pin "54") (pinfunction "GND10_54") (pintype "bidirectional"))
      (node (ref "U$1") (pin "64") (pinfunction "GND11_64") (pintype "bidirectional"))
      (node (ref "U$1") (pin "65") (pinfunction "GND12_65") (pintype "bidirectional"))
      (node (ref "U$1") (pin "67") (pinfunction "GND13_67") (pintype "bidirectional"))
      (node (ref "U$1") (pin "68") (pinfunction "GND14_68") (pintype "bidirectional"))
      (node (ref "U$1") (pin "8") (pinfunction "PWRKEY_8") (pintype "bidirectional"))
      (node (ref "U$13") (pin "2") (pinfunction "GND_2") (pintype "bidirectional"))
      (node (ref "U$16") (pin "22") (pinfunction "GND_22") (pintype "bidirectional"))
      (node (ref "U$16") (pin "53") (pinfunction "GND_53") (pintype "bidirectional"))
      (node (ref "U$16") (pin "6") (pinfunction "UGND_6") (pintype "bidirectional"))
      (node (ref "U$16") (pin "63") (pinfunction "GND_63") (pintype "bidirectional"))
      (node (ref "U$16") (pin "P$1") (pinfunction "GND_P$1") (pintype "bidirectional"))
      (node (ref "U$2") (pin "3") (pinfunction "GND_3") (pintype "bidirectional"))
      (node (ref "U$4") (pin "A1") (pinfunction "GND_A1") (pintype "bidirectional"))
      (node (ref "U$4") (pin "A12") (pinfunction "GND1_A12") (pintype "bidirectional"))
      (node (ref "U$4") (pin "B1") (pinfunction "GND2_B1") (pintype "bidirectional"))
      (node (ref "U$4") (pin "B12") (pinfunction "GND3_B12") (pintype "bidirectional"))
      (node (ref "U$5") (pin "1") (pinfunction "GND_1") (pintype "bidirectional"))
      (node (ref "U$6") (pin "2") (pinfunction "GND_2") (pintype "input"))
      (node (ref "U$6") (pin "4") (pinfunction "GND_4") (pintype "input"))
      (node (ref "U$8") (pin "2") (pinfunction "-_2") (pintype "passive"))
      (node (ref "U$9") (pin "3") (pinfunction "GND_3") (pintype "bidirectional"))
      (node (ref "U$9") (pin "4") (pinfunction "\\GND_4") (pintype "bidirectional"))
      (node (ref "U1") (pin "2") (pinfunction "VSS_2") (pintype "power_in"))
      (node (ref "UBT") (pin "P$13") (pinfunction "P$13_P$13") (pintype "bidirectional"))
      (node (ref "UBT") (pin "P$14") (pinfunction "P$14_P$14") (pintype "bidirectional"))
      (node (ref "UBT") (pin "P$19") (pinfunction "P$19_P$19") (pintype "bidirectional"))
      (node (ref "UBT") (pin "P$2") (pinfunction "P$2_P$2") (pintype "bidirectional"))
      (node (ref "X1") (pin "C5") (pinfunction "4_C5") (pintype "passive"))
      (node (ref "X2") (pin "1") (pinfunction "GND_1") (pintype "passive"))
      (node (ref "X2") (pin "2") (pinfunction "GND_2") (pintype "passive"))
      (node (ref "X3") (pin "9") (pinfunction "GND_9") (pintype "power_in"))
    )
    (net (code "51") (name "Net-(D1-BLUE_CATHODE)") (class "Default")
      (node (ref "D1") (pin "4") (pinfunction "BLUE_CATHODE_4") (pintype "bidirectional"))
      (node (ref "R11") (pin "1") (pinfunction "1_1") (pintype "passive"))
    )
    (net (code "52") (name "Net-(D1-GREEN_CATHODE)") (class "Default")
      (node (ref "D1") (pin "3") (pinfunction "GREEN_CATHODE_3") (pintype "bidirectional"))
      (node (ref "R14") (pin "1") (pinfunction "1_1") (pintype "passive"))
    )
    (net (code "53") (name "Net-(D1-RED_CATHODE)") (class "Default")
      (node (ref "D1") (pin "2") (pinfunction "RED_CATHODE_2") (pintype "bidirectional"))
      (node (ref "R15") (pin "1") (pinfunction "1_1") (pintype "passive"))
    )
    (net (code "54") (name "Net-(D2-PadC)") (class "Default")
      (node (ref "D2") (pin "C") (pinfunction "C_C") (pintype "passive"))
      (node (ref "R18") (pin "1") (pinfunction "1_1") (pintype "passive"))
    )
    (net (code "55") (name "Net-(D8-A)") (class "Default")
      (node (ref "D8") (pin "P$2") (pinfunction "A_P$2") (pintype "bidirectional"))
      (node (ref "U$13") (pin "1") (pinfunction "SW_1") (pintype "bidirectional"))
      (node (ref "U$7") (pin "2") (pinfunction "2_2") (pintype "passive"))
    )
    (net (code "56") (name "Net-(S1-3)") (class "Default")
      (node (ref "R3") (pin "2") (pinfunction "2_2") (pintype "passive"))
      (node (ref "S1") (pin "P3") (pinfunction "3_P3") (pintype "passive"))
      (node (ref "S1") (pin "P4") (pinfunction "4_P4") (pintype "passive"))
      (node (ref "U$16") (pin "43") (pinfunction "PE2_43") (pintype "bidirectional"))
    )
    (net (code "57") (name "Net-(S2-3)") (class "Default")
      (node (ref "S2") (pin "P3") (pinfunction "3_P3") (pintype "passive"))
      (node (ref "S2") (pin "P4") (pinfunction "4_P4") (pintype "passive"))
      (node (ref "U$16") (pin "20") (pinfunction "RESET_20") (pintype "bidirectional"))
    )
    (net (code "58") (name "Net-(U$1-GSM_RF_IN)") (class "Default")
      (node (ref "U$1") (pin "66") (pinfunction "GSM_RF_IN_66") (pintype "bidirectional"))
      (node (ref "X2") (pin "3") (pinfunction "SIGNAL_3") (pintype "passive"))
    )
    (net (code "59") (name "Net-(U$1-VRTC)") (class "Default")
      (node (ref "C12") (pin "2") (pinfunction "2_2") (pintype "passive"))
      (node (ref "U$1") (pin "17") (pinfunction "VRTC_17") (pintype "bidirectional"))
    )
    (net (code "60") (name "Net-(U$13-FB)") (class "Default")
      (node (ref "R12") (pin "1") (pinfunction "1_1") (pintype "passive"))
      (node (ref "R13") (pin "2") (pinfunction "2_2") (pintype "passive"))
      (node (ref "U$13") (pin "3") (pinfunction "FB_3") (pintype "bidirectional"))
    )
    (net (code "61") (name "Net-(U$16-AREF)") (class "Default")
      (node (ref "C7") (pin "1") (pinfunction "1_1") (pintype "passive"))
      (node (ref "U$16") (pin "62") (pinfunction "AREF_62") (pintype "bidirectional"))
    )
    (net (code "62") (name "Net-(U$16-UCAP)") (class "Default")
      (node (ref "C8") (pin "2") (pinfunction "2_2") (pintype "passive"))
      (node (ref "U$16") (pin "7") (pinfunction "UCAP_7") (pintype "bidirectional"))
    )
    (net (code "63") (name "Net-(U$16-XTAL1)") (class "Default")
      (node (ref "C5") (pin "2") (pinfunction "2_2") (pintype "passive"))
      (node (ref "U$16") (pin "24") (pinfunction "XTAL1_24") (pintype "bidirectional"))
      (node (ref "Y1") (pin "1") (pinfunction "1_1") (pintype "bidirectional"))
    )
    (net (code "64") (name "Net-(U$16-XTAL2)") (class "Default")
      (node (ref "C4") (pin "2") (pinfunction "2_2") (pintype "passive"))
      (node (ref "U$16") (pin "23") (pinfunction "XTAL2_23") (pintype "bidirectional"))
      (node (ref "Y1") (pin "3") (pinfunction "2_3") (pintype "bidirectional"))
    )
    (net (code "65") (name "Net-(U1-PROG)") (class "Default")
      (node (ref "R19") (pin "1") (pinfunction "1_1") (pintype "passive"))
      (node (ref "U1") (pin "5") (pinfunction "PROG_5") (pintype "input"))
    )
    (net (code "66") (name "Net-(U1-STAT)") (class "Default")
      (node (ref "R18") (pin "2") (pinfunction "2_2") (pintype "passive"))
      (node (ref "U1") (pin "1") (pinfunction "STAT_1") (pintype "output"))
    )
    (net (code "67") (name "Net-(X3-ADC)") (class "Default")
      (node (ref "R5") (pin "2") (pinfunction "2_2") (pintype "passive"))
      (node (ref "X3") (pin "2") (pinfunction "ADC_2") (pintype "passive"))
    )
    (net (code "68") (name "Net-(X3-GPIO0)") (class "Default")
      (node (ref "R6") (pin "1") (pinfunction "1_1") (pintype "passive"))
      (node (ref "X3") (pin "12") (pinfunction "GPIO0_12") (pintype "bidirectional"))
    )
    (net (code "69") (name "Net-(X3-GPIO2)") (class "Default")
      (node (ref "R21") (pin "1") (pinfunction "1_1") (pintype "passive"))
      (node (ref "X3") (pin "11") (pinfunction "GPIO2_11") (pintype "bidirectional"))
    )
    (net (code "70") (name "Net-(X3-GPIO15)") (class "Default")
      (node (ref "R7") (pin "2") (pinfunction "2_2") (pintype "passive"))
      (node (ref "X3") (pin "10") (pinfunction "GPIO15_10") (pintype "bidirectional"))
    )
    (net (code "71") (name "VBAT") (class "Default")
      (node (ref "C2") (pin "1") (pinfunction "1_1") (pintype "passive"))
      (node (ref "CON_BAT") (pin "2") (pinfunction "+_2") (pintype "bidirectional"))
      (node (ref "U1") (pin "3") (pinfunction "VBAT_3") (pintype "power_in"))
      (node (ref "U9") (pin "LS1") (pinfunction "LS1_LS1") (pintype "bidirectional"))
      (node (ref "U9") (pin "LS2") (pinfunction "LS2_LS2") (pintype "bidirectional"))
    )
    (net (code "72") (name "VBAT-A") (class "Default")
      (node (ref "C13") (pin "1") (pinfunction "1_1") (pintype "passive"))
      (node (ref "C14") (pin "1") (pinfunction "1_1") (pintype "passive"))
      (node (ref "C15") (pin "1") (pinfunction "1_1") (pintype "passive"))
      (node (ref "C19") (pin "2") (pinfunction "2_2") (pintype "passive"))
      (node (ref "C21") (pin "2") (pinfunction "2_2") (pintype "passive"))
      (node (ref "C26") (pin "A") (pinfunction "+_A") (pintype "passive"))
      (node (ref "D3") (pin "A") (pinfunction "A_A") (pintype "passive"))
      (node (ref "U$1") (pin "4") (pinfunction "VBAT_4") (pintype "bidirectional"))
      (node (ref "U$1") (pin "5") (pinfunction "VBAT1_5") (pintype "bidirectional"))
      (node (ref "U$1") (pin "6") (pinfunction "VBAT2_6") (pintype "bidirectional"))
      (node (ref "U$13") (pin "4") (pinfunction "~{SHDN}_4") (pintype "bidirectional"))
      (node (ref "U$13") (pin "5") (pinfunction "VIN_5") (pintype "bidirectional"))
      (node (ref "U$6") (pin "1") (pinfunction "IN_1") (pintype "input"))
      (node (ref "U$7") (pin "1") (pinfunction "1_1") (pintype "passive"))
      (node (ref "U9") (pin "C1") (pinfunction "COM1_C1") (pintype "bidirectional"))
      (node (ref "U9") (pin "C2") (pinfunction "COM2_C2") (pintype "bidirectional"))
    )
    (net (code "73") (name "VUSB") (class "Default")
      (node (ref "C6") (pin "2") (pinfunction "2_2") (pintype "passive"))
      (node (ref "D2") (pin "A") (pinfunction "A_A") (pintype "passive"))
      (node (ref "U$16") (pin "3") (pinfunction "UVCC_3") (pintype "bidirectional"))
      (node (ref "U$16") (pin "8") (pinfunction "VBUS_8") (pintype "bidirectional"))
      (node (ref "U$4") (pin "A4") (pinfunction "VBUS_A4") (pintype "bidirectional"))
      (node (ref "U1") (pin "4") (pinfunction "VDD_4") (pintype "power_in"))
    )
    (net (code "74") (name "unconnected-(CON_BAT-PAD1-PadNC1)") (class "Default")
      (node (ref "CON_BAT") (pin "NC1") (pinfunction "PAD1_NC1") (pintype "bidirectional"))
    )
    (net (code "75") (name "unconnected-(CON_BAT-PAD2-PadNC2)") (class "Default")
      (node (ref "CON_BAT") (pin "NC2") (pinfunction "PAD2_NC2") (pintype "bidirectional"))
    )
    (net (code "76") (name "unconnected-(D7-C5-Pad6)") (class "Default")
      (node (ref "D7") (pin "6") (pinfunction "C5_6") (pintype "passive"))
    )
    (net (code "77") (name "unconnected-(J1-1-PadDTR)") (class "Default")
      (node (ref "J1") (pin "DTR") (pinfunction "1_DTR") (pintype "passive"))
    )
    (net (code "78") (name "unconnected-(J1-5-PadCTS)") (class "Default")
      (node (ref "J1") (pin "CTS") (pinfunction "5_CTS") (pintype "passive"))
    )
    (net (code "79") (name "unconnected-(U$1-1PPS-Pad37)") (class "Default")
      (node (ref "U$1") (pin "37") (pinfunction "1PPS_37") (pintype "bidirectional"))
    )
    (net (code "80") (name "unconnected-(U$1-ADC1-Pad23)") (class "Default")
      (node (ref "U$1") (pin "23") (pinfunction "ADC1_23") (pintype "bidirectional"))
    )
    (net (code "81") (name "unconnected-(U$1-ADC2-Pad24)") (class "Default")
      (node (ref "U$1") (pin "24") (pinfunction "ADC2_24") (pintype "bidirectional"))
    )
    (net (code "82") (name "unconnected-(U$1-ANT_BT-Pad53)") (class "Default")
      (node (ref "U$1") (pin "53") (pinfunction "ANT_BT_53") (pintype "bidirectional"))
    )
    (net (code "83") (name "unconnected-(U$1-COL0-Pad62)") (class "Default")
      (node (ref "U$1") (pin "62") (pinfunction "COL0_62") (pintype "bidirectional"))
    )
    (net (code "84") (name "unconnected-(U$1-COL1-Pad61)") (class "Default")
      (node (ref "U$1") (pin "61") (pinfunction "COL1_61") (pintype "bidirectional"))
    )
    (net (code "85") (name "unconnected-(U$1-COL2-Pad60)") (class "Default")
      (node (ref "U$1") (pin "60") (pinfunction "COL2_60") (pintype "bidirectional"))
    )
    (net (code "86") (name "unconnected-(U$1-COL3-Pad59)") (class "Default")
      (node (ref "U$1") (pin "59") (pinfunction "COL3_59") (pintype "bidirectional"))
    )
    (net (code "87") (name "unconnected-(U$1-CTS-Pad12)") (class "Default")
      (node (ref "U$1") (pin "12") (pinfunction "CTS_12") (pintype "bidirectional"))
    )
    (net (code "88") (name "unconnected-(U$1-DCD-Pad11)") (class "Default")
      (node (ref "U$1") (pin "11") (pinfunction "DCD_11") (pintype "bidirectional"))
    )
    (net (code "89") (name "unconnected-(U$1-GPIO5-Pad43)") (class "Default")
      (node (ref "U$1") (pin "43") (pinfunction "GPIO5_43") (pintype "bidirectional"))
    )
    (net (code "90") (name "unconnected-(U$1-GPIO6-Pad44)") (class "Default")
      (node (ref "U$1") (pin "44") (pinfunction "GPIO6_44") (pintype "bidirectional"))
    )
    (net (code "91") (name "unconnected-(U$1-GPS_RF_IN-Pad35)") (class "Default")
      (node (ref "U$1") (pin "35") (pinfunction "GPS_RF_IN_35") (pintype "bidirectional"))
    )
    (net (code "92") (name "unconnected-(U$1-MIC1N-Pad20)") (class "Default")
      (node (ref "U$1") (pin "20") (pinfunction "MIC1N_20") (pintype "bidirectional"))
    )
    (net (code "93") (name "unconnected-(U$1-MIC1P-Pad19)") (class "Default")
      (node (ref "U$1") (pin "19") (pinfunction "MIC1P_19") (pintype "bidirectional"))
    )
    (net (code "94") (name "unconnected-(U$1-NETLIGHT-Pad50)") (class "Default")
      (node (ref "U$1") (pin "50") (pinfunction "NETLIGHT_50") (pintype "bidirectional"))
    )
    (net (code "95") (name "unconnected-(U$1-PCM_CLK-Pad46)") (class "Default")
      (node (ref "U$1") (pin "46") (pinfunction "PCM_CLK_46") (pintype "bidirectional"))
    )
    (net (code "96") (name "unconnected-(U$1-PCM_IN-Pad47)") (class "Default")
      (node (ref "U$1") (pin "47") (pinfunction "PCM_IN_47") (pintype "bidirectional"))
    )
    (net (code "97") (name "unconnected-(U$1-PCM_OUT-Pad48)") (class "Default")
      (node (ref "U$1") (pin "48") (pinfunction "PCM_OUT_48") (pintype "bidirectional"))
    )
    (net (code "98") (name "unconnected-(U$1-PCM_SYNC-Pad45)") (class "Default")
      (node (ref "U$1") (pin "45") (pinfunction "PCM_SYNC_45") (pintype "bidirectional"))
    )
    (net (code "99") (name "unconnected-(U$1-PWM1-Pad42)") (class "Default")
      (node (ref "U$1") (pin "42") (pinfunction "PWM1_42") (pintype "bidirectional"))
    )
    (net (code "100") (name "unconnected-(U$1-PWM2-Pad41)") (class "Default")
      (node (ref "U$1") (pin "41") (pinfunction "PWM2_41") (pintype "bidirectional"))
    )
    (net (code "101") (name "unconnected-(U$1-RF_SYNS-Pad63)") (class "Default")
      (node (ref "U$1") (pin "63") (pinfunction "RF_SYNS_63") (pintype "bidirectional"))
    )
    (net (code "102") (name "unconnected-(U$1-RI-Pad10)") (class "Default")
      (node (ref "U$1") (pin "10") (pinfunction "RI_10") (pintype "bidirectional"))
    )
    (net (code "103") (name "unconnected-(U$1-ROW0-Pad58)") (class "Default")
      (node (ref "U$1") (pin "58") (pinfunction "ROW0_58") (pintype "bidirectional"))
    )
    (net (code "104") (name "unconnected-(U$1-ROW1-Pad57)") (class "Default")
      (node (ref "U$1") (pin "57") (pinfunction "ROW1_57") (pintype "bidirectional"))
    )
    (net (code "105") (name "unconnected-(U$1-ROW2-Pad56)") (class "Default")
      (node (ref "U$1") (pin "56") (pinfunction "ROW2_56") (pintype "bidirectional"))
    )
    (net (code "106") (name "unconnected-(U$1-ROW3-Pad55)") (class "Default")
      (node (ref "U$1") (pin "55") (pinfunction "ROW3_55") (pintype "bidirectional"))
    )
    (net (code "107") (name "unconnected-(U$1-RTS-Pad13)") (class "Default")
      (node (ref "U$1") (pin "13") (pinfunction "RTS_13") (pintype "bidirectional"))
    )
    (net (code "108") (name "unconnected-(U$1-SCL-Pad39)") (class "Default")
      (node (ref "U$1") (pin "39") (pinfunction "SCL_39") (pintype "bidirectional"))
    )
    (net (code "109") (name "unconnected-(U$1-SDA-Pad38)") (class "Default")
      (node (ref "U$1") (pin "38") (pinfunction "SDA_38") (pintype "bidirectional"))
    )
    (net (code "110") (name "unconnected-(U$1-SIM_PRE-Pad33)") (class "Default")
      (node (ref "U$1") (pin "33") (pinfunction "SIM_PRE_33") (pintype "bidirectional"))
    )
    (net (code "111") (name "unconnected-(U$1-SPK1N-Pad22)") (class "Default")
      (node (ref "U$1") (pin "22") (pinfunction "SPK1N_22") (pintype "bidirectional"))
    )
    (net (code "112") (name "unconnected-(U$1-SPK1P-Pad21)") (class "Default")
      (node (ref "U$1") (pin "21") (pinfunction "SPK1P_21") (pintype "bidirectional"))
    )
    (net (code "113") (name "unconnected-(U$1-STATUS-Pad49)") (class "Default")
      (node (ref "U$1") (pin "49") (pinfunction "STATUS_49") (pintype "bidirectional"))
    )
    (net (code "114") (name "unconnected-(U$1-USB_DM-Pad27)") (class "Default")
      (node (ref "U$1") (pin "27") (pinfunction "USB_DM_27") (pintype "bidirectional"))
    )
    (net (code "115") (name "unconnected-(U$1-USB_DP-Pad26)") (class "Default")
      (node (ref "U$1") (pin "26") (pinfunction "USB_DP_26") (pintype "bidirectional"))
    )
    (net (code "116") (name "unconnected-(U$1-VBUS-Pad25)") (class "Default")
      (node (ref "U$1") (pin "25") (pinfunction "VBUS_25") (pintype "bidirectional"))
    )
    (net (code "117") (name "unconnected-(U$1-VDD_EXT-Pad7)") (class "Default")
      (node (ref "U$1") (pin "7") (pinfunction "VDD_EXT_7") (pintype "bidirectional"))
    )
    (net (code "118") (name "unconnected-(U$4-RX1+-PadB11)") (class "Default")
      (node (ref "U$4") (pin "B11") (pinfunction "RX1+_B11") (pintype "bidirectional"))
    )
    (net (code "119") (name "unconnected-(U$4-RX1--PadB10)") (class "Default")
      (node (ref "U$4") (pin "B10") (pinfunction "RX1-_B10") (pintype "bidirectional"))
    )
    (net (code "120") (name "unconnected-(U$4-RX2+-PadA11)") (class "Default")
      (node (ref "U$4") (pin "A11") (pinfunction "RX2+_A11") (pintype "bidirectional"))
    )
    (net (code "121") (name "unconnected-(U$4-RX2--PadA10)") (class "Default")
      (node (ref "U$4") (pin "A10") (pinfunction "RX2-_A10") (pintype "bidirectional"))
    )
    (net (code "122") (name "unconnected-(U$4-SBU1-PadA8)") (class "Default")
      (node (ref "U$4") (pin "A8") (pinfunction "SBU1_A8") (pintype "bidirectional"))
    )
    (net (code "123") (name "unconnected-(U$4-SBU2-PadB8)") (class "Default")
      (node (ref "U$4") (pin "B8") (pinfunction "SBU2_B8") (pintype "bidirectional"))
    )
    (net (code "124") (name "unconnected-(U$4-TX1+-PadA2)") (class "Default")
      (node (ref "U$4") (pin "A2") (pinfunction "TX1+_A2") (pintype "bidirectional"))
    )
    (net (code "125") (name "unconnected-(U$4-TX1--PadA3)") (class "Default")
      (node (ref "U$4") (pin "A3") (pinfunction "TX1-_A3") (pintype "bidirectional"))
    )
    (net (code "126") (name "unconnected-(U$4-TX2+-PadB2)") (class "Default")
      (node (ref "U$4") (pin "B2") (pinfunction "TX2+_B2") (pintype "bidirectional"))
    )
    (net (code "127") (name "unconnected-(U$4-TX2--PadB3)") (class "Default")
      (node (ref "U$4") (pin "B3") (pinfunction "TX2-_B3") (pintype "bidirectional"))
    )
    (net (code "128") (name "unconnected-(U$4-VBUS1-PadA9)") (class "Default")
      (node (ref "U$4") (pin "A9") (pinfunction "VBUS1_A9") (pintype "bidirectional"))
    )
    (net (code "129") (name "unconnected-(U$4-VBUS2-PadB4)") (class "Default")
      (node (ref "U$4") (pin "B4") (pinfunction "VBUS2_B4") (pintype "bidirectional"))
    )
    (net (code "130") (name "unconnected-(U$4-VBUS3-PadB9)") (class "Default")
      (node (ref "U$4") (pin "B9") (pinfunction "VBUS3_B9") (pintype "bidirectional"))
    )
    (net (code "131") (name "unconnected-(U$9-NC-Pad6)") (class "Default")
      (node (ref "U$9") (pin "6") (pinfunction "NC_6") (pintype "bidirectional"))
    )
    (net (code "132") (name "unconnected-(U$9-\\NC-Pad8)") (class "Default")
      (node (ref "U$9") (pin "8") (pinfunction "\\NC_8") (pintype "bidirectional"))
    )
    (net (code "133") (name "unconnected-(U$16-PA0-Pad51)") (class "Default")
      (node (ref "U$16") (pin "51") (pinfunction "PA0_51") (pintype "bidirectional"))
    )
    (net (code "134") (name "unconnected-(U$16-PA4-Pad47)") (class "Default")
      (node (ref "U$16") (pin "47") (pinfunction "PA4_47") (pintype "bidirectional"))
    )
    (net (code "135") (name "unconnected-(U$16-PA5-Pad46)") (class "Default")
      (node (ref "U$16") (pin "46") (pinfunction "PA5_46") (pintype "bidirectional"))
    )
    (net (code "136") (name "unconnected-(U$16-PB0-Pad10)") (class "Default")
      (node (ref "U$16") (pin "10") (pinfunction "PB0_10") (pintype "bidirectional"))
    )
    (net (code "137") (name "unconnected-(U$16-PB2-Pad12)") (class "Default")
      (node (ref "U$16") (pin "12") (pinfunction "PB2_12") (pintype "bidirectional"))
    )
    (net (code "138") (name "unconnected-(U$16-PB4-Pad14)") (class "Default")
      (node (ref "U$16") (pin "14") (pinfunction "PB4_14") (pintype "bidirectional"))
    )
    (net (code "139") (name "unconnected-(U$16-PB6-Pad16)") (class "Default")
      (node (ref "U$16") (pin "16") (pinfunction "PB6_16") (pintype "bidirectional"))
    )
    (net (code "140") (name "unconnected-(U$16-PC0-Pad35)") (class "Default")
      (node (ref "U$16") (pin "35") (pinfunction "PC0_35") (pintype "bidirectional"))
    )
    (net (code "141") (name "unconnected-(U$16-PC1-Pad36)") (class "Default")
      (node (ref "U$16") (pin "36") (pinfunction "PC1_36") (pintype "bidirectional"))
    )
    (net (code "142") (name "unconnected-(U$16-PC2-Pad37)") (class "Default")
      (node (ref "U$16") (pin "37") (pinfunction "PC2_37") (pintype "bidirectional"))
    )
    (net (code "143") (name "unconnected-(U$16-PC4-Pad39)") (class "Default")
      (node (ref "U$16") (pin "39") (pinfunction "PC4_39") (pintype "bidirectional"))
    )
    (net (code "144") (name "unconnected-(U$16-PC5-Pad40)") (class "Default")
      (node (ref "U$16") (pin "40") (pinfunction "PC5_40") (pintype "bidirectional"))
    )
    (net (code "145") (name "unconnected-(U$16-PC6-Pad41)") (class "Default")
      (node (ref "U$16") (pin "41") (pinfunction "PC6_41") (pintype "bidirectional"))
    )
    (net (code "146") (name "unconnected-(U$16-PC7-Pad42)") (class "Default")
      (node (ref "U$16") (pin "42") (pinfunction "PC7_42") (pintype "bidirectional"))
    )
    (net (code "147") (name "unconnected-(U$16-PD4-Pad29)") (class "Default")
      (node (ref "U$16") (pin "29") (pinfunction "PD4_29") (pintype "bidirectional"))
    )
    (net (code "148") (name "unconnected-(U$16-PD5-Pad30)") (class "Default")
      (node (ref "U$16") (pin "30") (pinfunction "PD5_30") (pintype "bidirectional"))
    )
    (net (code "149") (name "unconnected-(U$16-PD6-Pad31)") (class "Default")
      (node (ref "U$16") (pin "31") (pinfunction "PD6_31") (pintype "bidirectional"))
    )
    (net (code "150") (name "unconnected-(U$16-PD7-Pad32)") (class "Default")
      (node (ref "U$16") (pin "32") (pinfunction "PD7_32") (pintype "bidirectional"))
    )
    (net (code "151") (name "unconnected-(U$16-PE0-Pad33)") (class "Default")
      (node (ref "U$16") (pin "33") (pinfunction "PE0_33") (pintype "bidirectional"))
    )
    (net (code "152") (name "unconnected-(U$16-PE1-Pad34)") (class "Default")
      (node (ref "U$16") (pin "34") (pinfunction "PE1_34") (pintype "bidirectional"))
    )
    (net (code "153") (name "unconnected-(U$16-PE3-Pad9)") (class "Default")
      (node (ref "U$16") (pin "9") (pinfunction "PE3_9") (pintype "bidirectional"))
    )
    (net (code "154") (name "unconnected-(U$16-PE4-Pad18)") (class "Default")
      (node (ref "U$16") (pin "18") (pinfunction "PE4_18") (pintype "bidirectional"))
    )
    (net (code "155") (name "unconnected-(U$16-PE5-Pad19)") (class "Default")
      (node (ref "U$16") (pin "19") (pinfunction "PE5_19") (pintype "bidirectional"))
    )
    (net (code "156") (name "unconnected-(U$16-PE6-Pad1)") (class "Default")
      (node (ref "U$16") (pin "1") (pinfunction "PE6_1") (pintype "bidirectional"))
    )
    (net (code "157") (name "unconnected-(U$16-PE7-Pad2)") (class "Default")
      (node (ref "U$16") (pin "2") (pinfunction "PE7_2") (pintype "bidirectional"))
    )
    (net (code "158") (name "unconnected-(U$16-PF0-Pad61)") (class "Default")
      (node (ref "U$16") (pin "61") (pinfunction "PF0_61") (pintype "bidirectional"))
    )
    (net (code "159") (name "unconnected-(U$16-PF1-Pad60)") (class "Default")
      (node (ref "U$16") (pin "60") (pinfunction "PF1_60") (pintype "bidirectional"))
    )
    (net (code "160") (name "unconnected-(U$16-PF2-Pad59)") (class "Default")
      (node (ref "U$16") (pin "59") (pinfunction "PF2_59") (pintype "bidirectional"))
    )
    (net (code "161") (name "unconnected-(U9-PadM1)") (class "Default")
      (node (ref "U9") (pin "M1") (pinfunction "M1_M1") (pintype "bidirectional"))
    )
    (net (code "162") (name "unconnected-(U9-PadM2)") (class "Default")
      (node (ref "U9") (pin "M2") (pinfunction "M2_M2") (pintype "bidirectional"))
    )
    (net (code "163") (name "unconnected-(U9-PadRS1)") (class "Default")
      (node (ref "U9") (pin "RS1") (pinfunction "RS1_RS1") (pintype "bidirectional"))
    )
    (net (code "164") (name "unconnected-(U9-PadRS2)") (class "Default")
      (node (ref "U9") (pin "RS2") (pinfunction "RS2_RS2") (pintype "bidirectional"))
    )
    (net (code "165") (name "unconnected-(UBT-PadP$1)") (class "Default")
      (node (ref "UBT") (pin "P$1") (pinfunction "P$1_P$1") (pintype "bidirectional"))
    )
    (net (code "166") (name "unconnected-(UBT-PadP$3)") (class "Default")
      (node (ref "UBT") (pin "P$3") (pinfunction "P$3_P$3") (pintype "bidirectional"))
    )
    (net (code "167") (name "unconnected-(UBT-PadP$4)") (class "Default")
      (node (ref "UBT") (pin "P$4") (pinfunction "P$4_P$4") (pintype "bidirectional"))
    )
    (net (code "168") (name "unconnected-(UBT-PadP$5)") (class "Default")
      (node (ref "UBT") (pin "P$5") (pinfunction "P$5_P$5") (pintype "bidirectional"))
    )
    (net (code "169") (name "unconnected-(UBT-PadP$7)") (class "Default")
      (node (ref "UBT") (pin "P$7") (pinfunction "P$7_P$7") (pintype "bidirectional"))
    )
    (net (code "170") (name "unconnected-(UBT-PadP$8)") (class "Default")
      (node (ref "UBT") (pin "P$8") (pinfunction "P$8_P$8") (pintype "bidirectional"))
    )
    (net (code "171") (name "unconnected-(UBT-PadP$9)") (class "Default")
      (node (ref "UBT") (pin "P$9") (pinfunction "P$9_P$9") (pintype "bidirectional"))
    )
    (net (code "172") (name "unconnected-(UBT-PadP$10)") (class "Default")
      (node (ref "UBT") (pin "P$10") (pinfunction "P$10_P$10") (pintype "bidirectional"))
    )
    (net (code "173") (name "unconnected-(UBT-PadP$11)") (class "Default")
      (node (ref "UBT") (pin "P$11") (pinfunction "P$11_P$11") (pintype "bidirectional"))
    )
    (net (code "174") (name "unconnected-(UBT-PadP$15)") (class "Default")
      (node (ref "UBT") (pin "P$15") (pinfunction "P$15_P$15") (pintype "bidirectional"))
    )
    (net (code "175") (name "unconnected-(UBT-PadP$16)") (class "Default")
      (node (ref "UBT") (pin "P$16") (pinfunction "P$16_P$16") (pintype "bidirectional"))
    )
    (net (code "176") (name "unconnected-(UBT-PadP$17)") (class "Default")
      (node (ref "UBT") (pin "P$17") (pinfunction "P$17_P$17") (pintype "bidirectional"))
    )
    (net (code "177") (name "unconnected-(UBT-PadP$18)") (class "Default")
      (node (ref "UBT") (pin "P$18") (pinfunction "P$18_P$18") (pintype "bidirectional"))
    )
    (net (code "178") (name "unconnected-(UBT-PadP$22)") (class "Default")
      (node (ref "UBT") (pin "P$22") (pinfunction "P$22_P$22") (pintype "bidirectional"))
    )
    (net (code "179") (name "unconnected-(UBT-PadP$23)") (class "Default")
      (node (ref "UBT") (pin "P$23") (pinfunction "P$23_P$23") (pintype "bidirectional"))
    )
    (net (code "180") (name "unconnected-(UBT-PadP$24)") (class "Default")
      (node (ref "UBT") (pin "P$24") (pinfunction "P$24_P$24") (pintype "bidirectional"))
    )
    (net (code "181") (name "unconnected-(UBT-PadP$25)") (class "Default")
      (node (ref "UBT") (pin "P$25") (pinfunction "P$25_P$25") (pintype "bidirectional"))
    )
    (net (code "182") (name "unconnected-(UBT-PadP$26)") (class "Default")
      (node (ref "UBT") (pin "P$26") (pinfunction "P$26_P$26") (pintype "bidirectional"))
    )
    (net (code "183") (name "unconnected-(UBT-PadP$27)") (class "Default")
      (node (ref "UBT") (pin "P$27") (pinfunction "P$27_P$27") (pintype "bidirectional"))
    )
    (net (code "184") (name "unconnected-(UBT-PadP$28)") (class "Default")
      (node (ref "UBT") (pin "P$28") (pinfunction "P$28_P$28") (pintype "bidirectional"))
    )
    (net (code "185") (name "unconnected-(UBT-PadP$29)") (class "Default")
      (node (ref "UBT") (pin "P$29") (pinfunction "P$29_P$29") (pintype "bidirectional"))
    )
    (net (code "186") (name "unconnected-(UBT-PadP$30)") (class "Default")
      (node (ref "UBT") (pin "P$30") (pinfunction "P$30_P$30") (pintype "bidirectional"))
    )
    (net (code "187") (name "unconnected-(UBT-PadP$31)") (class "Default")
      (node (ref "UBT") (pin "P$31") (pinfunction "P$31_P$31") (pintype "bidirectional"))
    )
    (net (code "188") (name "unconnected-(UBT-PadP$32)") (class "Default")
      (node (ref "UBT") (pin "P$32") (pinfunction "P$32_P$32") (pintype "bidirectional"))
    )
    (net (code "189") (name "unconnected-(X1-5-PadC6)") (class "Default")
      (node (ref "X1") (pin "C6") (pinfunction "5_C6") (pintype "passive"))
    )
    (net (code "190") (name "unconnected-(X3-CH_PD-Pad3)") (class "Default")
      (node (ref "X3") (pin "3") (pinfunction "CH_PD_3") (pintype "input"))
    )
    (net (code "191") (name "unconnected-(X3-GPIO4-Pad14)") (class "Default")
      (node (ref "X3") (pin "14") (pinfunction "GPIO4_14") (pintype "bidirectional"))
    )
    (net (code "192") (name "unconnected-(X3-GPIO5-Pad13)") (class "Default")
      (node (ref "X3") (pin "13") (pinfunction "GPIO5_13") (pintype "bidirectional"))
    )
    (net (code "193") (name "unconnected-(X3-GPIO12-Pad6)") (class "Default")
      (node (ref "X3") (pin "6") (pinfunction "GPIO12_6") (pintype "bidirectional"))
    )
    (net (code "194") (name "unconnected-(X3-GPIO13-Pad7)") (class "Default")
      (node (ref "X3") (pin "7") (pinfunction "GPIO13_7") (pintype "bidirectional"))
    )
    (net (code "195") (name "unconnected-(X3-GPIO14-Pad5)") (class "Default")
      (node (ref "X3") (pin "5") (pinfunction "GPIO14_5") (pintype "bidirectional"))
    )
  )
)
